# cpu.net
KiCad netlist of a schematic drawn in EAGLE
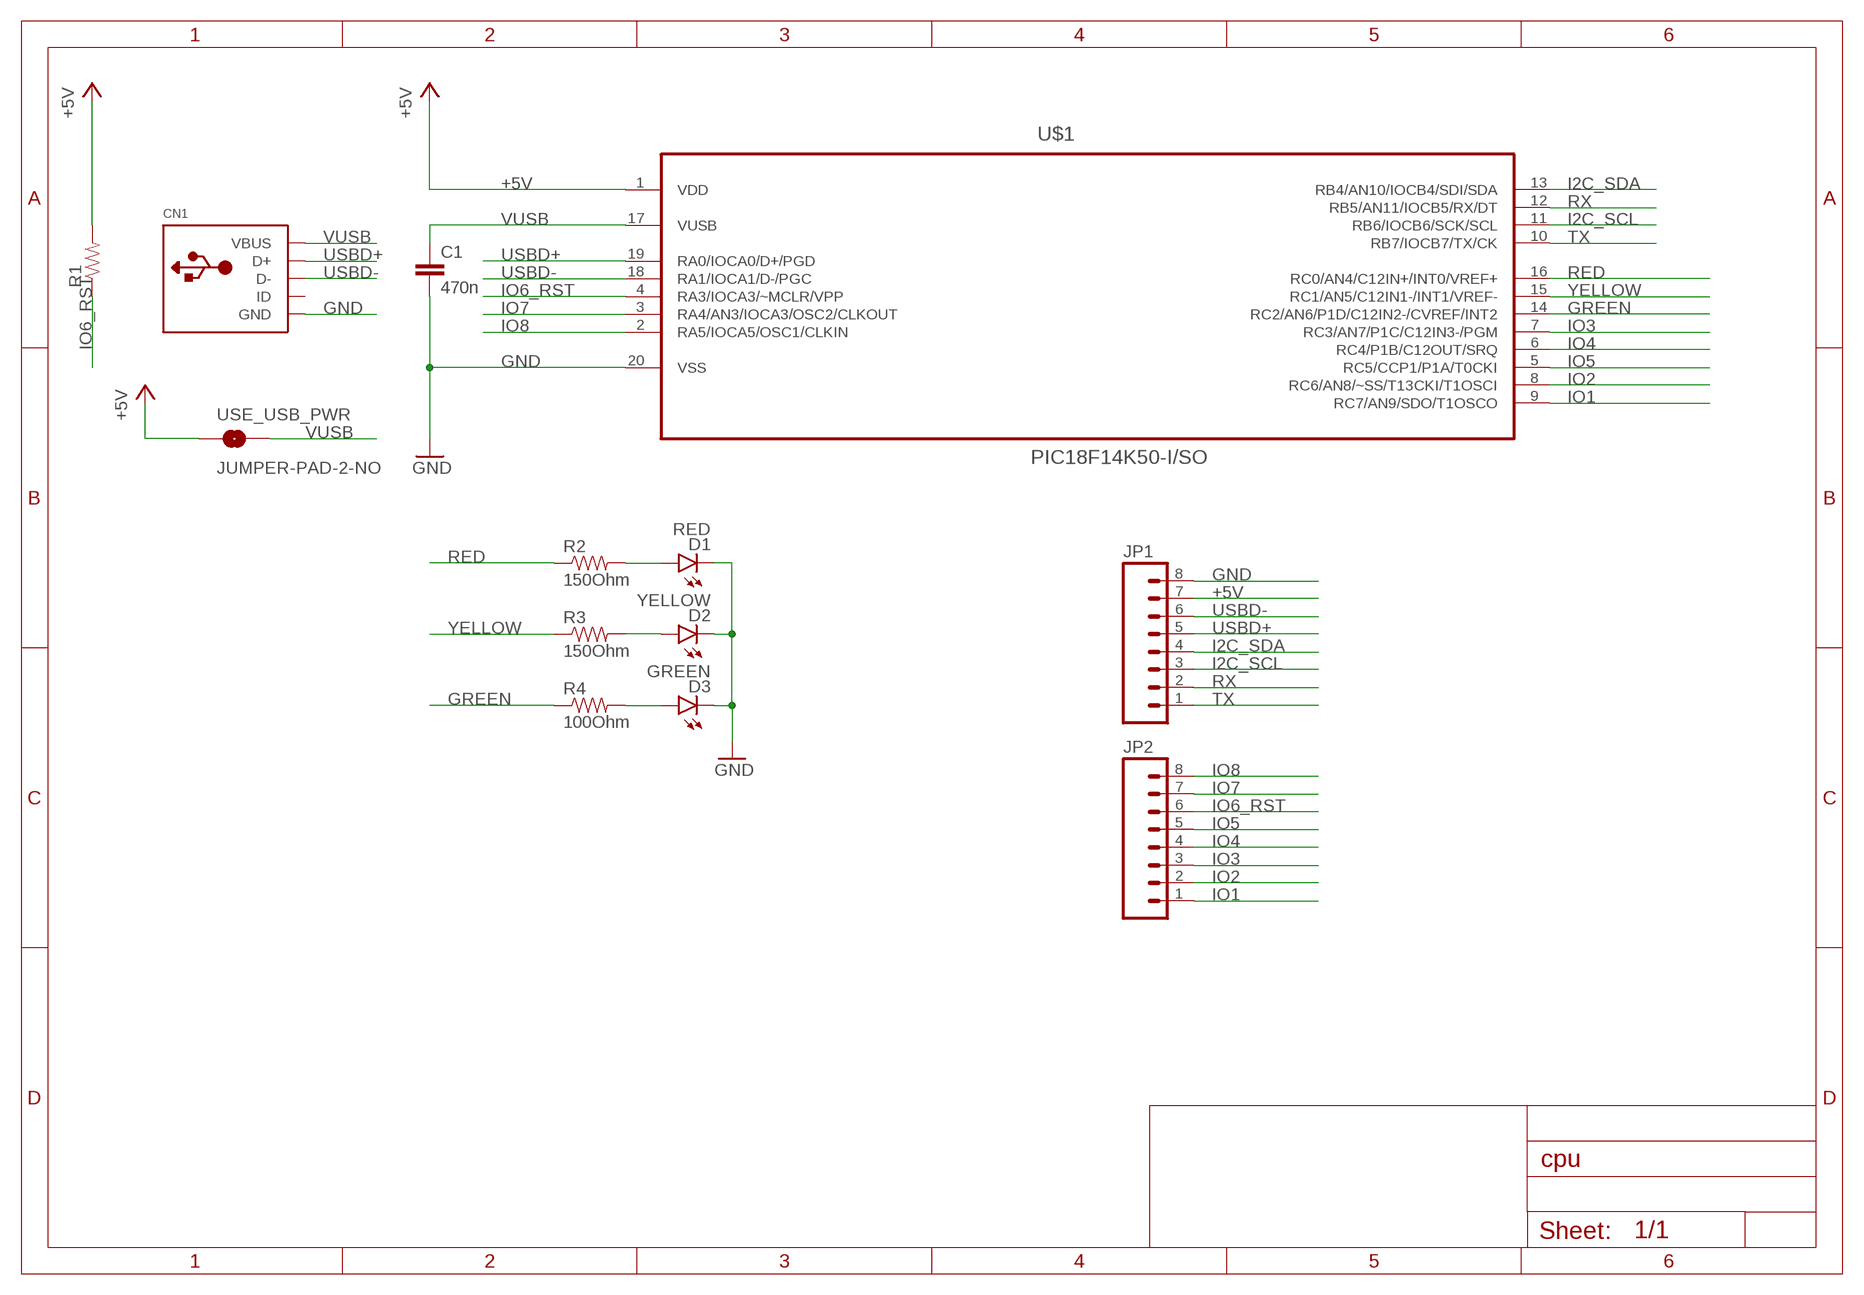
[diagram p0: schematic, sheet 1]

(export (version "E")
  (design (tool "Eeschema 10.0.6"))
  (components
    (comp (ref "C1")
      (value "470n")
      (footprint "eagle-import:C0805K")
      (libsource (lib "eagle-import") (part "C-EUC0805K"))
    )
    (comp (ref "CN1")
      (value "USBMINIB")
      (footprint "eagle-import:USB-MINIB")
      (libsource (lib "eagle-import") (part "USBMINIB"))
    )
    (comp (ref "D1")
      (value "RED")
      (footprint "eagle-import:LED-0603")
      (libsource (lib "eagle-import") (part "LED-RED0603"))
    )
    (comp (ref "D2")
      (value "YELLOW")
      (footprint "eagle-import:LED-0603")
      (libsource (lib "eagle-import") (part "LED-YELLOW0603"))
    )
    (comp (ref "D3")
      (value "GREEN")
      (footprint "eagle-import:LED-0603")
      (libsource (lib "eagle-import") (part "LED-GREEN0603"))
    )
    (comp (ref "JP1")
      (value "M081X08")
      (footprint "eagle-import:1X08")
      (libsource (lib "eagle-import") (part "M081X08"))
    )
    (comp (ref "JP2")
      (value "M081X08")
      (footprint "eagle-import:1X08")
      (libsource (lib "eagle-import") (part "M081X08"))
    )
    (comp (ref "R1")
      (value "RESISTOR0402-RES")
      (footprint "eagle-import:0402-RES")
      (libsource (lib "eagle-import") (part "RESISTOR0402-RES"))
    )
    (comp (ref "R2")
      (value "150Ohm")
      (footprint "eagle-import:0402-RES")
      (libsource (lib "eagle-import") (part "RESISTOR0402-RES"))
    )
    (comp (ref "R3")
      (value "150Ohm")
      (footprint "eagle-import:0402-RES")
      (libsource (lib "eagle-import") (part "RESISTOR0402-RES"))
    )
    (comp (ref "R4")
      (value "100Ohm")
      (footprint "eagle-import:0402-RES")
      (libsource (lib "eagle-import") (part "RESISTOR0402-RES"))
    )
    (comp (ref "U$1")
      (value "PIC18F14K50-I/SO")
      (footprint "eagle-import:SOIC127P1030X265-20N")
      (libsource (lib "eagle-import") (part "PIC18F14K50-I/SO"))
    )
    (comp (ref "USE_USB_PWR")
      (value "JUMPER-PAD-2-NO")
      (footprint "eagle-import:PAD-JUMPER-2-NO_NO_SILK")
      (libsource (lib "eagle-import") (part "JUMPER-PAD-2-NO"))
    )
  )
  (nets
    (net (code "1") (name "+5V") (class "Default")
      (node (ref "JP1") (pin "7") (pinfunction "7_7") (pintype "passive"))
      (node (ref "R1") (pin "2") (pinfunction "2_2") (pintype "passive"))
      (node (ref "U$1") (pin "1") (pinfunction "VDD_1") (pintype "power_in"))
      (node (ref "USE_USB_PWR") (pin "1") (pinfunction "1_1") (pintype "passive"))
    )
    (net (code "2") (name "/GREEN") (class "Default")
      (node (ref "R4") (pin "1") (pinfunction "1_1") (pintype "passive"))
      (node (ref "U$1") (pin "14") (pinfunction "RC2/AN6/P1D/C12IN2-/CVREF/INT2_14") (pintype "bidirectional"))
    )
    (net (code "3") (name "/I2C_SCL") (class "Default")
      (node (ref "JP1") (pin "3") (pinfunction "3_3") (pintype "passive"))
      (node (ref "U$1") (pin "11") (pinfunction "RB6/IOCB6/SCK/SCL_11") (pintype "bidirectional"))
    )
    (net (code "4") (name "/I2C_SDA") (class "Default")
      (node (ref "JP1") (pin "4") (pinfunction "4_4") (pintype "passive"))
      (node (ref "U$1") (pin "13") (pinfunction "RB4/AN10/IOCB4/SDI/SDA_13") (pintype "bidirectional"))
    )
    (net (code "5") (name "/IO1") (class "Default")
      (node (ref "JP2") (pin "1") (pinfunction "1_1") (pintype "passive"))
      (node (ref "U$1") (pin "9") (pinfunction "RC7/AN9/SDO/T1OSCO_9") (pintype "bidirectional"))
    )
    (net (code "6") (name "/IO2") (class "Default")
      (node (ref "JP2") (pin "2") (pinfunction "2_2") (pintype "passive"))
      (node (ref "U$1") (pin "8") (pinfunction "RC6/AN8/~{SS/T13CKI/T1OSCI}_8") (pintype "bidirectional"))
    )
    (net (code "7") (name "/IO3") (class "Default")
      (node (ref "JP2") (pin "3") (pinfunction "3_3") (pintype "passive"))
      (node (ref "U$1") (pin "7") (pinfunction "RC3/AN7/P1C/C12IN3-/PGM_7") (pintype "bidirectional"))
    )
    (net (code "8") (name "/IO4") (class "Default")
      (node (ref "JP2") (pin "4") (pinfunction "4_4") (pintype "passive"))
      (node (ref "U$1") (pin "6") (pinfunction "RC4/P1B/C12OUT/SRQ_6") (pintype "bidirectional"))
    )
    (net (code "9") (name "/IO5") (class "Default")
      (node (ref "JP2") (pin "5") (pinfunction "5_5") (pintype "passive"))
      (node (ref "U$1") (pin "5") (pinfunction "RC5/CCP1/P1A/T0CKI_5") (pintype "bidirectional"))
    )
    (net (code "10") (name "/IO6_RST") (class "Default")
      (node (ref "JP2") (pin "6") (pinfunction "6_6") (pintype "passive"))
      (node (ref "R1") (pin "1") (pinfunction "1_1") (pintype "passive"))
      (node (ref "U$1") (pin "4") (pinfunction "RA3/IOCA3/~{MCLR/VPP}_4") (pintype "bidirectional"))
    )
    (net (code "11") (name "/IO7") (class "Default")
      (node (ref "JP2") (pin "7") (pinfunction "7_7") (pintype "passive"))
      (node (ref "U$1") (pin "3") (pinfunction "RA4/AN3/IOCA3/OSC2/CLKOUT_3") (pintype "input"))
    )
    (net (code "12") (name "/IO8") (class "Default")
      (node (ref "JP2") (pin "8") (pinfunction "8_8") (pintype "passive"))
      (node (ref "U$1") (pin "2") (pinfunction "RA5/IOCA5/OSC1/CLKIN_2") (pintype "bidirectional"))
    )
    (net (code "13") (name "/RED") (class "Default")
      (node (ref "R2") (pin "1") (pinfunction "1_1") (pintype "passive"))
      (node (ref "U$1") (pin "16") (pinfunction "RC0/AN4/C12IN+/INT0/VREF+_16") (pintype "power_in"))
    )
    (net (code "14") (name "/RX") (class "Default")
      (node (ref "JP1") (pin "2") (pinfunction "2_2") (pintype "passive"))
      (node (ref "U$1") (pin "12") (pinfunction "RB5/AN11/IOCB5/RX/DT_12") (pintype "bidirectional"))
    )
    (net (code "15") (name "/TX") (class "Default")
      (node (ref "JP1") (pin "1") (pinfunction "1_1") (pintype "passive"))
      (node (ref "U$1") (pin "10") (pinfunction "RB7/IOCB7/TX/CK_10") (pintype "bidirectional"))
    )
    (net (code "16") (name "/USBD+") (class "Default")
      (node (ref "CN1") (pin "D+") (pinfunction "D+_D+") (pintype "bidirectional"))
      (node (ref "JP1") (pin "5") (pinfunction "5_5") (pintype "passive"))
      (node (ref "U$1") (pin "19") (pinfunction "RA0/IOCA0/D+/PGD_19") (pintype "bidirectional"))
    )
    (net (code "17") (name "/USBD-") (class "Default")
      (node (ref "CN1") (pin "D-") (pinfunction "D-_D-") (pintype "bidirectional"))
      (node (ref "JP1") (pin "6") (pinfunction "6_6") (pintype "passive"))
      (node (ref "U$1") (pin "18") (pinfunction "RA1/IOCA1/D-/PGC_18") (pintype "bidirectional"))
    )
    (net (code "18") (name "/VUSB") (class "Default")
      (node (ref "C1") (pin "1") (pinfunction "1_1") (pintype "passive"))
      (node (ref "CN1") (pin "VBUS") (pinfunction "VBUS_VBUS") (pintype "power_in"))
      (node (ref "U$1") (pin "17") (pinfunction "VUSB_17") (pintype "input"))
      (node (ref "USE_USB_PWR") (pin "2") (pinfunction "2_2") (pintype "passive"))
    )
    (net (code "19") (name "/YELLOW") (class "Default")
      (node (ref "R3") (pin "1") (pinfunction "1_1") (pintype "passive"))
      (node (ref "U$1") (pin "15") (pinfunction "RC1/AN5/C12IN1-/INT1/VREF-_15") (pintype "power_in"))
    )
    (net (code "20") (name "GND") (class "Default")
      (node (ref "C1") (pin "2") (pinfunction "2_2") (pintype "passive"))
      (node (ref "CN1") (pin "GND") (pinfunction "GND_GND") (pintype "power_in"))
      (node (ref "D1") (pin "C") (pinfunction "C_C") (pintype "passive"))
      (node (ref "D2") (pin "C") (pinfunction "C_C") (pintype "passive"))
      (node (ref "D3") (pin "C") (pinfunction "C_C") (pintype "passive"))
      (node (ref "JP1") (pin "8") (pinfunction "8_8") (pintype "passive"))
      (node (ref "U$1") (pin "20") (pinfunction "VSS_20") (pintype "passive"))
    )
    (net (code "21") (name "Net-(D1-PadA)") (class "Default")
      (node (ref "D1") (pin "A") (pinfunction "A_A") (pintype "passive"))
      (node (ref "R2") (pin "2") (pinfunction "2_2") (pintype "passive"))
    )
    (net (code "22") (name "Net-(D2-PadA)") (class "Default")
      (node (ref "D2") (pin "A") (pinfunction "A_A") (pintype "passive"))
      (node (ref "R3") (pin "2") (pinfunction "2_2") (pintype "passive"))
    )
    (net (code "23") (name "Net-(D3-PadA)") (class "Default")
      (node (ref "D3") (pin "A") (pinfunction "A_A") (pintype "passive"))
      (node (ref "R4") (pin "2") (pinfunction "2_2") (pintype "passive"))
    )
    (net (code "24") (name "unconnected-(CN1-PadID)") (class "Default")
      (node (ref "CN1") (pin "ID") (pinfunction "ID_ID") (pintype "bidirectional"))
    )
  )
)
